# Example.net
KiCad netlist of a schematic drawn in EAGLE
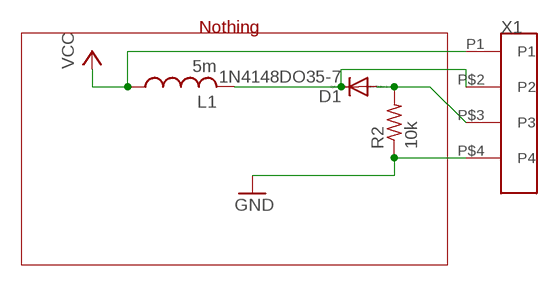
[diagram p0: schematic, sheet 1]

(export (version "E")
  (design (tool "Eeschema 10.0.6"))
  (components
    (comp (ref "D1")
      (value "1N4148DO35-7")
      (footprint "eagle-import:DO35-7")
      (libsource (lib "eagle-import") (part "1N4148DO35-7"))
    )
    (comp (ref "L1")
      (value "5m")
      (footprint "eagle-import:L3225P")
      (libsource (lib "eagle-import") (part "L-USL3225P"))
    )
    (comp (ref "R2")
      (value "10k")
      (footprint "eagle-import:M0805")
      (libsource (lib "eagle-import") (part "R-US_M0805"))
    )
    (comp (ref "X1")
      (value "TE-952")
      (footprint "eagle-import:TE-952")
      (libsource (lib "eagle-import") (part "TE-952"))
    )
  )
  (nets
    (net (code "1") (name "GND") (class "Default")
      (node (ref "R2") (pin "1") (pinfunction "1_1") (pintype "passive"))
      (node (ref "X1") (pin "P$4") (pinfunction "P4_P$4") (pintype "bidirectional"))
    )
    (net (code "2") (name "Net-(X1-P2)") (class "Default")
      (node (ref "D1") (pin "C") (pinfunction "C_C") (pintype "passive"))
      (node (ref "L1") (pin "2") (pinfunction "2_2") (pintype "passive"))
      (node (ref "X1") (pin "P$2") (pinfunction "P2_P$2") (pintype "bidirectional"))
    )
    (net (code "3") (name "Net-(X1-P3)") (class "Default")
      (node (ref "D1") (pin "A") (pinfunction "A_A") (pintype "passive"))
      (node (ref "R2") (pin "2") (pinfunction "2_2") (pintype "passive"))
      (node (ref "X1") (pin "P$3") (pinfunction "P3_P$3") (pintype "bidirectional"))
    )
    (net (code "4") (name "VCC") (class "Default")
      (node (ref "L1") (pin "1") (pinfunction "1_1") (pintype "passive"))
      (node (ref "X1") (pin "P1") (pinfunction "P1_P1") (pintype "bidirectional"))
    )
  )
)
